# longranger-001.net
KiCad netlist of a schematic drawn in EAGLE
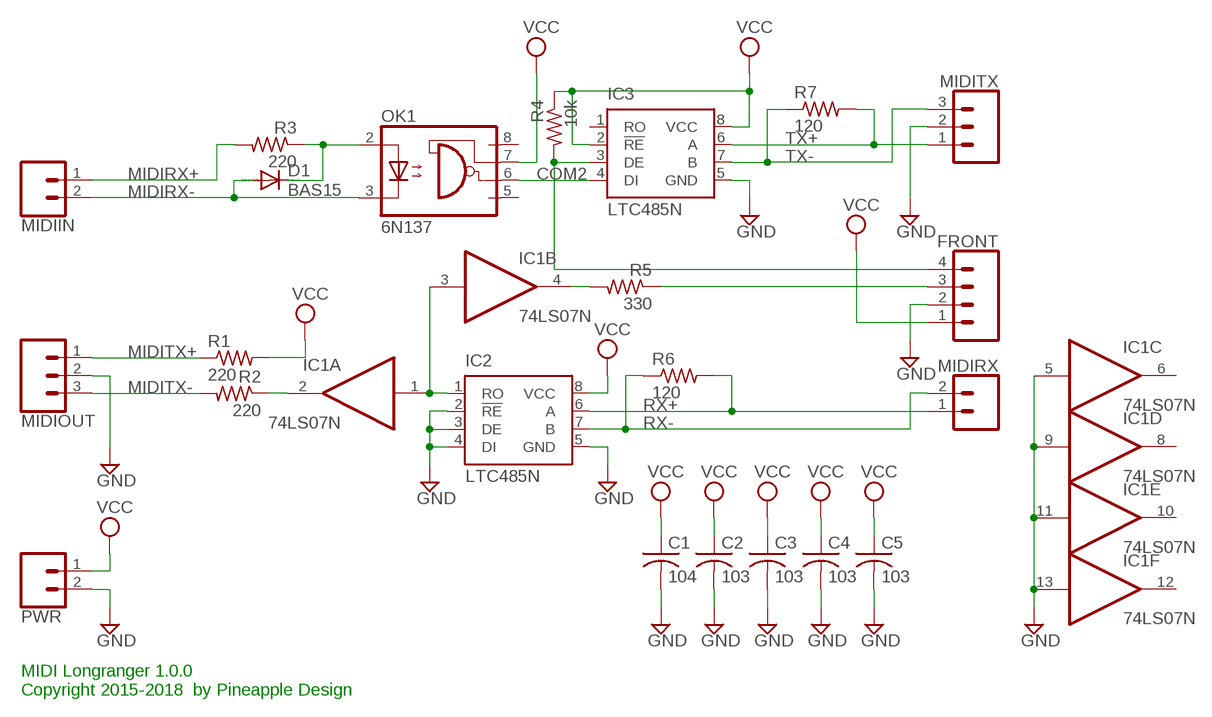
[diagram p0: schematic, sheet 1]

(export (version "E")
  (design (tool "Eeschema 10.0.6"))
  (components
    (comp (ref "C1")
      (value "104")
      (footprint "eagle-import:C025-025X050")
      (libsource (lib "eagle-import") (part "C-US025-025X050"))
    )
    (comp (ref "C2")
      (value "103")
      (footprint "eagle-import:C025-025X050")
      (libsource (lib "eagle-import") (part "C-US025-025X050"))
    )
    (comp (ref "C3")
      (value "103")
      (footprint "eagle-import:C025-025X050")
      (libsource (lib "eagle-import") (part "C-US025-025X050"))
    )
    (comp (ref "C4")
      (value "103")
      (footprint "eagle-import:C025-025X050")
      (libsource (lib "eagle-import") (part "C-US025-025X050"))
    )
    (comp (ref "C5")
      (value "103")
      (footprint "eagle-import:C025-025X050")
      (libsource (lib "eagle-import") (part "C-US025-025X050"))
    )
    (comp (ref "D1")
      (value "BAS15")
      (footprint "eagle-import:DO34-7")
      (libsource (lib "eagle-import") (part "BAS15"))
    )
    (comp (ref "FRONT")
      (value "CONN_04JST-PTH")
      (footprint "eagle-import:JST-4-PTH")
      (libsource (lib "eagle-import") (part "CONN_04JST-PTH"))
    )
    (comp (ref "IC1")
      (value "74LS07N")
      (footprint "eagle-import:DIL14")
      (libsource (lib "eagle-import") (part "7407NLS"))
    )
    (comp (ref "IC2")
      (value "LTC485N")
      (footprint "eagle-import:DIL08")
      (libsource (lib "eagle-import") (part "LTC485N"))
    )
    (comp (ref "IC3")
      (value "LTC485N")
      (footprint "eagle-import:DIL08")
      (libsource (lib "eagle-import") (part "LTC485N"))
    )
    (comp (ref "MIDIIN")
      (value "CONN_02JST-PTH-2")
      (footprint "eagle-import:JST-2-PTH")
      (libsource (lib "eagle-import") (part "CONN_02JST-PTH-2"))
    )
    (comp (ref "MIDIOUT")
      (value "CONN_03JST-PTH")
      (footprint "eagle-import:JST-3-PTH")
      (libsource (lib "eagle-import") (part "CONN_03JST-PTH"))
    )
    (comp (ref "MIDIRX")
      (value "CONN_02JST-PTH-2")
      (footprint "eagle-import:JST-2-PTH")
      (libsource (lib "eagle-import") (part "CONN_02JST-PTH-2"))
    )
    (comp (ref "MIDITX")
      (value "CONN_03JST-PTH")
      (footprint "eagle-import:JST-3-PTH")
      (libsource (lib "eagle-import") (part "CONN_03JST-PTH"))
    )
    (comp (ref "OK1")
      (value "6N137")
      (footprint "eagle-import:DIL08")
      (libsource (lib "eagle-import") (part "6N137"))
    )
    (comp (ref "PWR")
      (value "CONN_02JST-PTH-2")
      (footprint "eagle-import:JST-2-PTH")
      (libsource (lib "eagle-import") (part "CONN_02JST-PTH-2"))
    )
    (comp (ref "R1")
      (value "220")
      (footprint "eagle-import:0204_5")
      (libsource (lib "eagle-import") (part "R-US_0204/5"))
    )
    (comp (ref "R2")
      (value "220")
      (footprint "eagle-import:0204_5")
      (libsource (lib "eagle-import") (part "R-US_0204/5"))
    )
    (comp (ref "R3")
      (value "220")
      (footprint "eagle-import:0204_5")
      (libsource (lib "eagle-import") (part "R-US_0204/5"))
    )
    (comp (ref "R4")
      (value "10k")
      (footprint "eagle-import:0204_5")
      (libsource (lib "eagle-import") (part "R-US_0204/5"))
    )
    (comp (ref "R5")
      (value "330")
      (footprint "eagle-import:0204_5")
      (libsource (lib "eagle-import") (part "R-US_0204/5"))
    )
    (comp (ref "R6")
      (value "120")
      (footprint "eagle-import:0204_5")
      (libsource (lib "eagle-import") (part "R-US_0204/5"))
    )
    (comp (ref "R7")
      (value "120")
      (footprint "eagle-import:0204_5")
      (libsource (lib "eagle-import") (part "R-US_0204/5"))
    )
  )
  (nets
    (net (code "1") (name "/COM2") (class "Default")
      (node (ref "IC3") (pin "4") (pinfunction "DI_4") (pintype "input"))
      (node (ref "OK1") (pin "6") (pinfunction "VO_6") (pintype "passive"))
    )
    (net (code "2") (name "/MIDIRX+") (class "Default")
      (node (ref "MIDIIN") (pin "1") (pinfunction "1_1") (pintype "passive"))
      (node (ref "R3") (pin "2") (pinfunction "2_2") (pintype "passive"))
    )
    (net (code "3") (name "/MIDIRX-") (class "Default")
      (node (ref "D1") (pin "A") (pinfunction "A_A") (pintype "passive"))
      (node (ref "MIDIIN") (pin "2") (pinfunction "2_2") (pintype "passive"))
      (node (ref "OK1") (pin "3") (pinfunction "C_3") (pintype "passive"))
    )
    (net (code "4") (name "/MIDITX+") (class "Default")
      (node (ref "MIDIOUT") (pin "1") (pinfunction "1_1") (pintype "passive"))
      (node (ref "R1") (pin "1") (pinfunction "1_1") (pintype "passive"))
    )
    (net (code "5") (name "/MIDITX-") (class "Default")
      (node (ref "MIDIOUT") (pin "3") (pinfunction "3_3") (pintype "passive"))
      (node (ref "R2") (pin "2") (pinfunction "2_2") (pintype "passive"))
    )
    (net (code "6") (name "/RX+") (class "Default")
      (node (ref "IC2") (pin "6") (pinfunction "A_6") (pintype "bidirectional"))
      (node (ref "MIDIRX") (pin "1") (pinfunction "1_1") (pintype "passive"))
      (node (ref "R6") (pin "2") (pinfunction "2_2") (pintype "passive"))
    )
    (net (code "7") (name "/RX-") (class "Default")
      (node (ref "IC2") (pin "7") (pinfunction "B_7") (pintype "bidirectional"))
      (node (ref "MIDIRX") (pin "2") (pinfunction "2_2") (pintype "passive"))
      (node (ref "R6") (pin "1") (pinfunction "1_1") (pintype "passive"))
    )
    (net (code "8") (name "/TX+") (class "Default")
      (node (ref "IC3") (pin "6") (pinfunction "A_6") (pintype "bidirectional"))
      (node (ref "MIDITX") (pin "1") (pinfunction "1_1") (pintype "passive"))
      (node (ref "R7") (pin "2") (pinfunction "2_2") (pintype "passive"))
    )
    (net (code "9") (name "/TX-") (class "Default")
      (node (ref "IC3") (pin "7") (pinfunction "B_7") (pintype "bidirectional"))
      (node (ref "MIDITX") (pin "3") (pinfunction "3_3") (pintype "passive"))
      (node (ref "R7") (pin "1") (pinfunction "1_1") (pintype "passive"))
    )
    (net (code "10") (name "GND") (class "Default")
      (node (ref "C1") (pin "2") (pinfunction "2_2") (pintype "passive"))
      (node (ref "C2") (pin "2") (pinfunction "2_2") (pintype "passive"))
      (node (ref "C3") (pin "2") (pinfunction "2_2") (pintype "passive"))
      (node (ref "C4") (pin "2") (pinfunction "2_2") (pintype "passive"))
      (node (ref "C5") (pin "2") (pinfunction "2_2") (pintype "passive"))
      (node (ref "FRONT") (pin "2") (pinfunction "2_2") (pintype "passive"))
      (node (ref "IC1") (pin "11") (pinfunction "I_11") (pintype "input"))
      (node (ref "IC1") (pin "13") (pinfunction "I_13") (pintype "input"))
      (node (ref "IC1") (pin "5") (pinfunction "I_5") (pintype "input"))
      (node (ref "IC1") (pin "9") (pinfunction "I_9") (pintype "input"))
      (node (ref "IC2") (pin "2") (pinfunction "~{RE}_2") (pintype "input"))
      (node (ref "IC2") (pin "3") (pinfunction "DE_3") (pintype "input"))
      (node (ref "IC2") (pin "4") (pinfunction "DI_4") (pintype "input"))
      (node (ref "IC2") (pin "5") (pinfunction "GND_5") (pintype "input"))
      (node (ref "IC3") (pin "5") (pinfunction "GND_5") (pintype "input"))
      (node (ref "MIDIOUT") (pin "2") (pinfunction "2_2") (pintype "passive"))
      (node (ref "MIDITX") (pin "2") (pinfunction "2_2") (pintype "passive"))
      (node (ref "PWR") (pin "2") (pinfunction "2_2") (pintype "passive"))
    )
    (net (code "11") (name "Net-(FRONT-Pad3)") (class "Default")
      (node (ref "FRONT") (pin "3") (pinfunction "3_3") (pintype "passive"))
      (node (ref "R5") (pin "1") (pinfunction "1_1") (pintype "passive"))
    )
    (net (code "12") (name "Net-(IC1A-I)") (class "Default")
      (node (ref "IC1") (pin "1") (pinfunction "I_1") (pintype "input"))
      (node (ref "IC1") (pin "3") (pinfunction "I_3") (pintype "input"))
      (node (ref "IC2") (pin "1") (pinfunction "RO_1") (pintype "output"))
    )
    (net (code "13") (name "Net-(IC1A-O)") (class "Default")
      (node (ref "IC1") (pin "2") (pinfunction "O_2") (pintype "open_collector"))
      (node (ref "R2") (pin "1") (pinfunction "1_1") (pintype "passive"))
    )
    (net (code "14") (name "Net-(IC1B-O)") (class "Default")
      (node (ref "IC1") (pin "4") (pinfunction "O_4") (pintype "open_collector"))
      (node (ref "R5") (pin "2") (pinfunction "2_2") (pintype "passive"))
    )
    (net (code "15") (name "Net-(IC3-DE)") (class "Default")
      (node (ref "FRONT") (pin "4") (pinfunction "4_4") (pintype "passive"))
      (node (ref "IC3") (pin "3") (pinfunction "DE_3") (pintype "input"))
      (node (ref "R4") (pin "2") (pinfunction "2_2") (pintype "passive"))
    )
    (net (code "16") (name "Net-(OK1-A)") (class "Default")
      (node (ref "D1") (pin "C") (pinfunction "C_C") (pintype "passive"))
      (node (ref "OK1") (pin "2") (pinfunction "A_2") (pintype "passive"))
      (node (ref "R3") (pin "1") (pinfunction "1_1") (pintype "passive"))
    )
    (net (code "17") (name "VCC") (class "Default")
      (node (ref "C1") (pin "1") (pinfunction "1_1") (pintype "passive"))
      (node (ref "C2") (pin "1") (pinfunction "1_1") (pintype "passive"))
      (node (ref "C3") (pin "1") (pinfunction "1_1") (pintype "passive"))
      (node (ref "C4") (pin "1") (pinfunction "1_1") (pintype "passive"))
      (node (ref "C5") (pin "1") (pinfunction "1_1") (pintype "passive"))
      (node (ref "FRONT") (pin "1") (pinfunction "1_1") (pintype "passive"))
      (node (ref "IC2") (pin "8") (pinfunction "VCC_8") (pintype "input"))
      (node (ref "IC3") (pin "2") (pinfunction "~{RE}_2") (pintype "input"))
      (node (ref "IC3") (pin "8") (pinfunction "VCC_8") (pintype "input"))
      (node (ref "OK1") (pin "7") (pinfunction "VE_7") (pintype "passive"))
      (node (ref "PWR") (pin "1") (pinfunction "1_1") (pintype "passive"))
      (node (ref "R1") (pin "2") (pinfunction "2_2") (pintype "passive"))
      (node (ref "R4") (pin "1") (pinfunction "1_1") (pintype "passive"))
    )
    (net (code "18") (name "unconnected-(IC1C-O-Pad6)") (class "Default")
      (node (ref "IC1") (pin "6") (pinfunction "O_6") (pintype "open_collector"))
    )
    (net (code "19") (name "unconnected-(IC1D-O-Pad8)") (class "Default")
      (node (ref "IC1") (pin "8") (pinfunction "O_8") (pintype "open_collector"))
    )
    (net (code "20") (name "unconnected-(IC1E-O-Pad10)") (class "Default")
      (node (ref "IC1") (pin "10") (pinfunction "O_10") (pintype "open_collector"))
    )
    (net (code "21") (name "unconnected-(IC1F-O-Pad12)") (class "Default")
      (node (ref "IC1") (pin "12") (pinfunction "O_12") (pintype "open_collector"))
    )
    (net (code "22") (name "unconnected-(IC3-RO-Pad1)") (class "Default")
      (node (ref "IC3") (pin "1") (pinfunction "RO_1") (pintype "output"))
    )
    (net (code "23") (name "unconnected-(OK1-GND-Pad5)") (class "Default")
      (node (ref "OK1") (pin "5") (pinfunction "GND_5") (pintype "passive"))
    )
    (net (code "24") (name "unconnected-(OK1-VCC-Pad8)") (class "Default")
      (node (ref "OK1") (pin "8") (pinfunction "VCC_8") (pintype "passive"))
    )
  )
)
